# Boost.net
KiCad netlist of a schematic drawn in Altium Designer
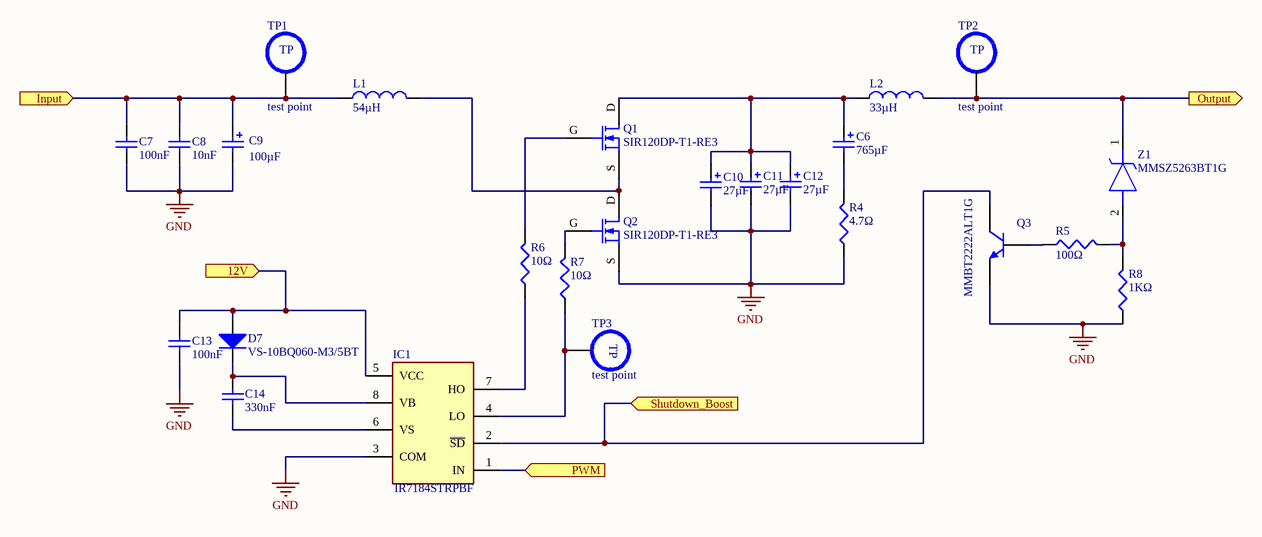
[diagram p0: Boost.SchDoc]

(export (version "E")
  (design (tool "Eeschema 10.0.6"))
  (components
    (comp (ref "C6")
      (value "765µF")
      (footprint "PcbLib1:EEE0JA471UAP")
      (description "Capacitor Polarised")
      (fields
        (field (name "MANUFACTURER_PART_NUMBER") "EEV-FK1K101V")
        (field (name "MOUSER PART NUMBER") "667-EEV-FK1K101V")
      )
      (libsource (lib "Schlib1") (part "765µF"))
    )
    (comp (ref "C7")
      (value "100nF")
      (footprint "PcbLib1:CAPC3216X180N")
      (description "Capacitor")
      (fields (field (name "PUBLISHER") "Altium Limited"))
      (libsource (lib "Schlib1") (part "100nF"))
    )
    (comp (ref "C8")
      (value "10nF")
      (footprint "PcbLib1:CAPC3216X180N")
      (description "Capacitor")
      (fields (field (name "PUBLISHER") "Altium Limited"))
      (libsource (lib "Schlib1") (part "10nF"))
    )
    (comp (ref "C9")
      (value "100µF")
      (footprint "PcbLib1:EEE0JA471UAP")
      (description "Capacitor Polarised")
      (fields
        (field (name "MANUFACTURER_PART_NUMBER") "EEV-FK1K101V")
        (field (name "MOUSER PART NUMBER") "667-EEV-FK1K101V")
      )
      (libsource (lib "Schlib1") (part "100µF"))
    )
    (comp (ref "C10")
      (value "27µF")
      (footprint "PcbLib1:EEE0JA471UAP")
      (description "Capacitor Polarised")
      (fields
        (field (name "MANUFACTURER_PART_NUMBER") "EEV-FK1K101V")
        (field (name "MOUSER PART NUMBER") "667-EEV-FK1K101V")
      )
      (libsource (lib "Schlib1") (part "27µF"))
    )
    (comp (ref "C11")
      (value "27µF")
      (footprint "PcbLib1:EEE0JA471UAP")
      (description "Capacitor Polarised")
      (fields
        (field (name "MANUFACTURER_PART_NUMBER") "EEV-FK1K101V")
        (field (name "MOUSER PART NUMBER") "667-EEV-FK1K101V")
      )
      (libsource (lib "Schlib1") (part "27µF"))
    )
    (comp (ref "C12")
      (value "27µF")
      (footprint "PcbLib1:EEE0JA471UAP")
      (description "Capacitor Polarised")
      (fields
        (field (name "MANUFACTURER_PART_NUMBER") "EEV-FK1K101V")
        (field (name "MOUSER PART NUMBER") "667-EEV-FK1K101V")
      )
      (libsource (lib "Schlib1") (part "27µF"))
    )
    (comp (ref "C13")
      (value "100nF")
      (footprint "PcbLib1:CAPC3216X180N")
      (description "Capacitor")
      (fields (field (name "PUBLISHER") "Altium Limited"))
      (libsource (lib "Schlib1") (part "100nF"))
    )
    (comp (ref "C14")
      (value "330nF")
      (footprint "PcbLib1:CAPC3216X180N")
      (description "Capacitor")
      (fields (field (name "PUBLISHER") "Altium Limited"))
      (libsource (lib "Schlib1") (part "330nF"))
    )
    (comp (ref "D7")
      (value "VS-10BQ060-M3/5BT")
      (footprint "PcbLib1:DIOM5436X244N")
      (description "Default Diode")
      (fields (field (name "PUBLISHER") "Altium Limited"))
      (libsource (lib "Schlib1") (part "Diode"))
    )
    (comp (ref "IC1")
      (value "IR7184STRPBF")
      (footprint "PcbLib1:SOIC127P600X175-8N")
      (description "Integrated Circuit")
      (fields (field (name "MOUSER PART NUMBER") "942-IR7184STRPBF"))
      (libsource (lib "Schlib1") (part "IR7184STRPBF"))
    )
    (comp (ref "L1")
      (value "54µH")
      (footprint "PcbLib1:SHBC201R7A0152V")
      (description "power inductor")
      (libsource (lib "Schlib1") (part "54µH"))
    )
    (comp (ref "L2")
      (value "33µH")
      (footprint "PcbLib1:INDPM125125X850N")
      (description "power inductor")
      (libsource (lib "Schlib1") (part "33µH"))
    )
    (comp (ref "Q1")
      (value "SIR120DP-T1-RE3")
      (footprint "SamacSys:SI7141DPT1GE3")
      (description "MOSFET (N-Channel)")
      (fields (field (name "MOUSER PART NUMBER") "78-SIR120DP-T1-RE3"))
      (libsource (lib "Schlib1") (part "SIR120DP-T1-RE3"))
    )
    (comp (ref "Q2")
      (value "SIR120DP-T1-RE3")
      (footprint "SamacSys:SI7141DPT1GE3")
      (description "MOSFET (N-Channel)")
      (fields (field (name "MOUSER PART NUMBER") "78-SIR120DP-T1-RE3"))
      (libsource (lib "Schlib1") (part "SIR120DP-T1-RE3"))
    )
    (comp (ref "Q3")
      (value "MMBT2222ALT1G")
      (footprint "PcbLib1:SOT96P237X111-3N")
      (description "NPN Bipolar Transistor")
      (fields (field (name "PUBLISHER") "Altium Limited"))
      (libsource (lib "Schlib1") (part "NPN"))
    )
    (comp (ref "R4")
      (value "4.7Ω")
      (footprint "PcbLib1:RESC3216X75N")
      (description "Resistor")
      (fields (field (name "PUBLISHER") "Altium Limited"))
      (libsource (lib "Schlib1") (part "4.7Ω"))
    )
    (comp (ref "R5")
      (value "100Ω")
      (footprint "PcbLib1:RESC3216X75N")
      (description "Resistor")
      (fields (field (name "PUBLISHER") "Altium Limited"))
      (libsource (lib "Schlib1") (part "100Ω"))
    )
    (comp (ref "R6")
      (value "10Ω")
      (footprint "PcbLib1:RESC3216X75N")
      (description "Resistor")
      (fields (field (name "PUBLISHER") "Altium Limited"))
      (libsource (lib "Schlib1") (part "10Ω"))
    )
    (comp (ref "R7")
      (value "10Ω")
      (footprint "PcbLib1:RESC3216X75N")
      (description "Resistor")
      (fields (field (name "PUBLISHER") "Altium Limited"))
      (libsource (lib "Schlib1") (part "10Ω"))
    )
    (comp (ref "R8")
      (value "1KΩ")
      (footprint "PcbLib1:RESC3216X75N")
      (description "Resistor")
      (fields (field (name "PUBLISHER") "Altium Limited"))
      (libsource (lib "Schlib1") (part "1KΩ"))
    )
    (comp (ref "TP1")
      (value "test point")
      (footprint "PcbLib1:Test point")
      (libsource (lib "Schlib1") (part "test point"))
    )
    (comp (ref "TP2")
      (value "test point")
      (footprint "PcbLib1:Test point")
      (libsource (lib "Schlib1") (part "test point"))
    )
    (comp (ref "TP3")
      (value "test point")
      (footprint "PcbLib1:Test point")
      (libsource (lib "Schlib1") (part "test point"))
    )
    (comp (ref "Z1")
      (value "MMSZ5263BT1G")
      (footprint "PcbLib1:SOD3716X135N")
      (description "Zener Diode")
      (fields (field (name "MOUSER PART NUMBER") "863-MMSZ5263BT1G"))
      (libsource (lib "Schlib1") (part "MMSZ5263BT1G"))
    )
  )
  (nets
    (net (code "1") (name "/12V") (class "Default")
      (node (ref "C13") (pin "2") (pinfunction "2_2") (pintype "passive"))
      (node (ref "D7") (pin "1") (pinfunction "A_1") (pintype "passive"))
      (node (ref "IC1") (pin "5") (pinfunction "VCC_5") (pintype "passive"))
    )
    (net (code "2") (name "/Input") (class "Default")
      (node (ref "C7") (pin "2") (pinfunction "2_2") (pintype "passive"))
      (node (ref "C8") (pin "2") (pinfunction "2_2") (pintype "passive"))
      (node (ref "C9") (pin "1") (pinfunction "1_1") (pintype "passive"))
      (node (ref "L1") (pin "1") (pinfunction "1_1") (pintype "passive"))
      (node (ref "TP1") (pin "5") (pinfunction "5_5") (pintype "passive"))
    )
    (net (code "3") (name "/Output") (class "Default")
      (node (ref "L2") (pin "2") (pinfunction "2_2") (pintype "passive"))
      (node (ref "TP2") (pin "5") (pinfunction "5_5") (pintype "passive"))
      (node (ref "Z1") (pin "1") (pinfunction "K_1") (pintype "passive"))
    )
    (net (code "4") (name "/PWM") (class "Default")
      (node (ref "IC1") (pin "1") (pinfunction "IN_1") (pintype "passive"))
    )
    (net (code "5") (name "/Shutdown_Boost") (class "Default")
      (node (ref "IC1") (pin "2") (pinfunction "~{SD}_2") (pintype "passive"))
      (node (ref "Q3") (pin "1") (pinfunction "C_1") (pintype "passive"))
    )
    (net (code "6") (name "GND") (class "Default")
      (node (ref "C10") (pin "2") (pinfunction "2_2") (pintype "passive"))
      (node (ref "C11") (pin "2") (pinfunction "2_2") (pintype "passive"))
      (node (ref "C12") (pin "2") (pinfunction "2_2") (pintype "passive"))
      (node (ref "C13") (pin "1") (pinfunction "1_1") (pintype "passive"))
      (node (ref "C7") (pin "1") (pinfunction "1_1") (pintype "passive"))
      (node (ref "C8") (pin "1") (pinfunction "1_1") (pintype "passive"))
      (node (ref "C9") (pin "2") (pinfunction "2_2") (pintype "passive"))
      (node (ref "IC1") (pin "3") (pinfunction "COM_3") (pintype "passive"))
      (node (ref "Q2") (pin "S") (pinfunction "S_S") (pintype "passive"))
      (node (ref "Q3") (pin "3") (pinfunction "E_3") (pintype "passive"))
      (node (ref "R4") (pin "1") (pinfunction "1_1") (pintype "passive"))
      (node (ref "R8") (pin "1") (pinfunction "1_1") (pintype "passive"))
    )
    (net (code "7") (name "Net-(C6-Pad2)") (class "Default")
      (node (ref "C6") (pin "2") (pinfunction "2_2") (pintype "passive"))
      (node (ref "R4") (pin "2") (pinfunction "2_2") (pintype "passive"))
    )
    (net (code "8") (name "Net-(C10-Pad1)") (class "Default")
      (node (ref "C10") (pin "1") (pinfunction "1_1") (pintype "passive"))
      (node (ref "C11") (pin "1") (pinfunction "1_1") (pintype "passive"))
      (node (ref "C12") (pin "1") (pinfunction "1_1") (pintype "passive"))
      (node (ref "C6") (pin "1") (pinfunction "1_1") (pintype "passive"))
      (node (ref "L2") (pin "1") (pinfunction "1_1") (pintype "passive"))
      (node (ref "Q1") (pin "D") (pinfunction "D_D") (pintype "passive"))
    )
    (net (code "9") (name "Net-(D7-K)") (class "Default")
      (node (ref "C14") (pin "2") (pinfunction "2_2") (pintype "passive"))
      (node (ref "D7") (pin "2") (pinfunction "K_2") (pintype "passive"))
      (node (ref "IC1") (pin "8") (pinfunction "VB_8") (pintype "passive"))
    )
    (net (code "10") (name "Net-(IC1-HO)") (class "Default")
      (node (ref "IC1") (pin "7") (pinfunction "HO_7") (pintype "passive"))
      (node (ref "R6") (pin "1") (pinfunction "1_1") (pintype "passive"))
    )
    (net (code "11") (name "Net-(IC1-LO)") (class "Default")
      (node (ref "IC1") (pin "4") (pinfunction "LO_4") (pintype "passive"))
      (node (ref "R7") (pin "1") (pinfunction "1_1") (pintype "passive"))
      (node (ref "TP3") (pin "5") (pinfunction "5_5") (pintype "passive"))
    )
    (net (code "12") (name "Net-(IC1-VS)") (class "Default")
      (node (ref "C14") (pin "1") (pinfunction "1_1") (pintype "passive"))
      (node (ref "IC1") (pin "6") (pinfunction "VS_6") (pintype "passive"))
    )
    (net (code "13") (name "Net-(L1-Pad2)") (class "Default")
      (node (ref "L1") (pin "2") (pinfunction "2_2") (pintype "passive"))
      (node (ref "Q1") (pin "S") (pinfunction "S_S") (pintype "passive"))
      (node (ref "Q2") (pin "D") (pinfunction "D_D") (pintype "passive"))
    )
    (net (code "14") (name "Net-(Q1-PadG)") (class "Default")
      (node (ref "Q1") (pin "G") (pinfunction "G_G") (pintype "passive"))
      (node (ref "R6") (pin "2") (pinfunction "2_2") (pintype "passive"))
    )
    (net (code "15") (name "Net-(Q2-PadG)") (class "Default")
      (node (ref "Q2") (pin "G") (pinfunction "G_G") (pintype "passive"))
      (node (ref "R7") (pin "2") (pinfunction "2_2") (pintype "passive"))
    )
    (net (code "16") (name "Net-(Q3-B)") (class "Default")
      (node (ref "Q3") (pin "2") (pinfunction "B_2") (pintype "passive"))
      (node (ref "R5") (pin "1") (pinfunction "1_1") (pintype "passive"))
    )
    (net (code "17") (name "Net-(Z1-A)") (class "Default")
      (node (ref "R5") (pin "2") (pinfunction "2_2") (pintype "passive"))
      (node (ref "R8") (pin "2") (pinfunction "2_2") (pintype "passive"))
      (node (ref "Z1") (pin "2") (pinfunction "A_2") (pintype "passive"))
    )
  )
)
